# Accelerometer.net
KiCad netlist of a schematic drawn in Altium Designer
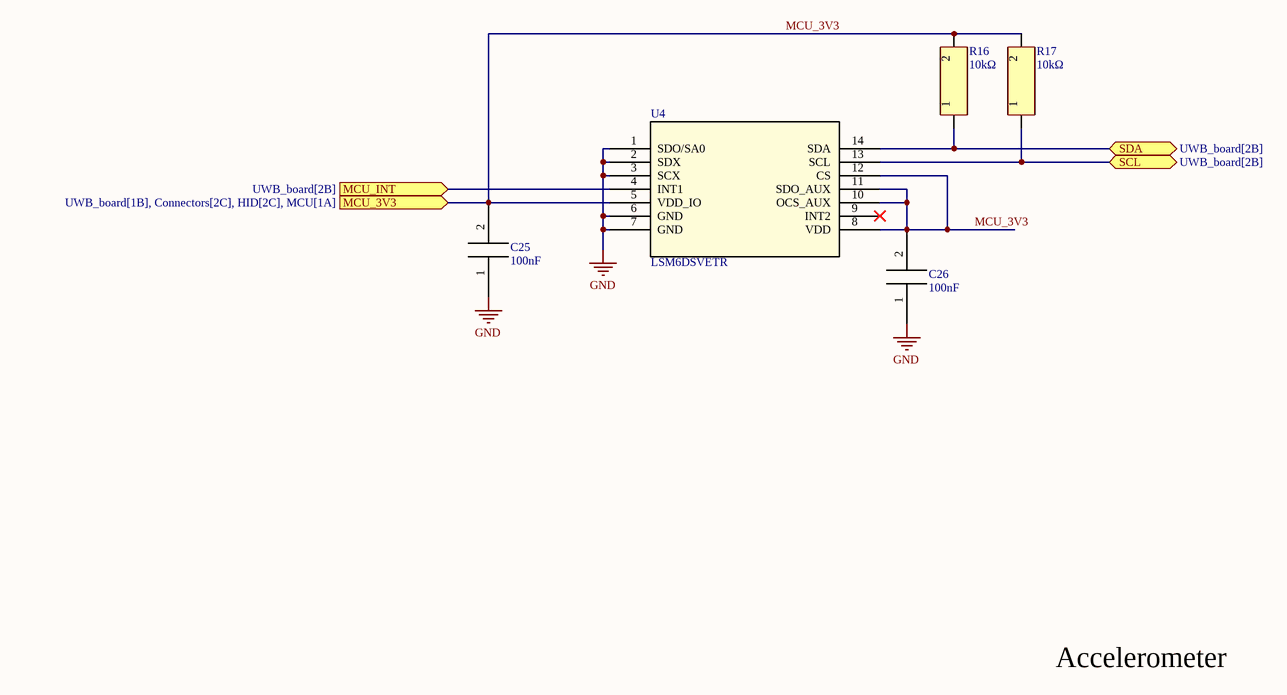
[diagram p0: Accelerometer.SchDoc]

(export (version "E")
  (design (tool "Eeschema 10.0.6"))
  (components
    (comp (ref "C25")
      (value "100nF")
      (footprint "0603_cap")
      (description "100nF 50V X7R ±10% 0603 Multilayer Ceramic Capacitors MLCC - SMD/SMT ROHS")
      (fields (field (name "LCSC PART #") "C14663"))
      (libsource (lib "Schlib1") (part "CC0603KRX7R9BB104"))
    )
    (comp (ref "C26")
      (value "100nF")
      (footprint "0603_cap")
      (description "100nF 50V X7R ±10% 0603 Multilayer Ceramic Capacitors MLCC - SMD/SMT ROHS")
      (fields (field (name "LCSC PART #") "C14663"))
      (libsource (lib "Schlib1") (part "CC0603KRX7R9BB104"))
    )
    (comp (ref "R16")
      (value "10kΩ")
      (footprint "0603_res")
      (fields (field (name "LCSC PART #") "C25804") (field (name "Comment") "10k"))
      (libsource (lib "Schlib1") (part "0603WAF1002T5E"))
    )
    (comp (ref "R17")
      (value "10kΩ")
      (footprint "0603_res")
      (fields (field (name "LCSC PART #") "C25804") (field (name "Comment") "10k"))
      (libsource (lib "Schlib1") (part "0603WAF1002T5E"))
    )
    (comp (ref "U4")
      (value "LSM6DSVETR")
      (footprint "LGA14-L_2p59x3P1x0P5_STM")
      (description "6-axis IMU with embedded sensor fusion, I3C, OIS/EIS for smart applications")
      (fields (field (name "LCSC PART #") "C41785564"))
      (libsource (lib "Schlib1") (part "LSM6DSVETR"))
    )
  )
  (nets
    (net (code "1") (name "/MCU_3V3") (class "Default")
      (node (ref "C25") (pin "2") (pinfunction "3_2") (pintype "passive"))
      (node (ref "C26") (pin "2") (pinfunction "3_2") (pintype "passive"))
      (node (ref "R16") (pin "2") (pinfunction "3_2") (pintype "passive"))
      (node (ref "R17") (pin "2") (pinfunction "3_2") (pintype "passive"))
      (node (ref "U4") (pin "10") (pinfunction "OCS_AUX_10") (pintype "passive"))
      (node (ref "U4") (pin "11") (pinfunction "SDO_AUX_11") (pintype "passive"))
      (node (ref "U4") (pin "12") (pinfunction "CS_12") (pintype "passive"))
      (node (ref "U4") (pin "5") (pinfunction "VDD_IO_5") (pintype "power_in"))
      (node (ref "U4") (pin "8") (pinfunction "VDD_8") (pintype "power_in"))
    )
    (net (code "2") (name "/MCU_INT") (class "Default")
      (node (ref "U4") (pin "4") (pinfunction "INT1_4") (pintype "passive"))
    )
    (net (code "3") (name "/SCL") (class "Default")
      (node (ref "R17") (pin "1") (pinfunction "1_1") (pintype "passive"))
      (node (ref "U4") (pin "13") (pinfunction "SCL_13") (pintype "passive"))
    )
    (net (code "4") (name "/SDA") (class "Default")
      (node (ref "R16") (pin "1") (pinfunction "1_1") (pintype "passive"))
      (node (ref "U4") (pin "14") (pinfunction "SDA_14") (pintype "passive"))
    )
    (net (code "5") (name "GND") (class "Default")
      (node (ref "C25") (pin "1") (pintype "passive"))
      (node (ref "C26") (pin "1") (pintype "passive"))
      (node (ref "U4") (pin "1") (pinfunction "SDO/SA0_1") (pintype "passive"))
      (node (ref "U4") (pin "2") (pinfunction "SDX_2") (pintype "passive"))
      (node (ref "U4") (pin "3") (pinfunction "SCX_3") (pintype "passive"))
      (node (ref "U4") (pin "6") (pinfunction "GND_6") (pintype "power_in"))
      (node (ref "U4") (pin "7") (pinfunction "GND_7") (pintype "power_in"))
    )
    (net (code "6") (name "unconnected-(U4-INT2-Pad9)") (class "Default")
      (node (ref "U4") (pin "9") (pinfunction "INT2_9") (pintype "passive+no_connect"))
    )
  )
)
